# xy_plotter_circuit.net
KiCad netlist of a schematic drawn in EAGLE
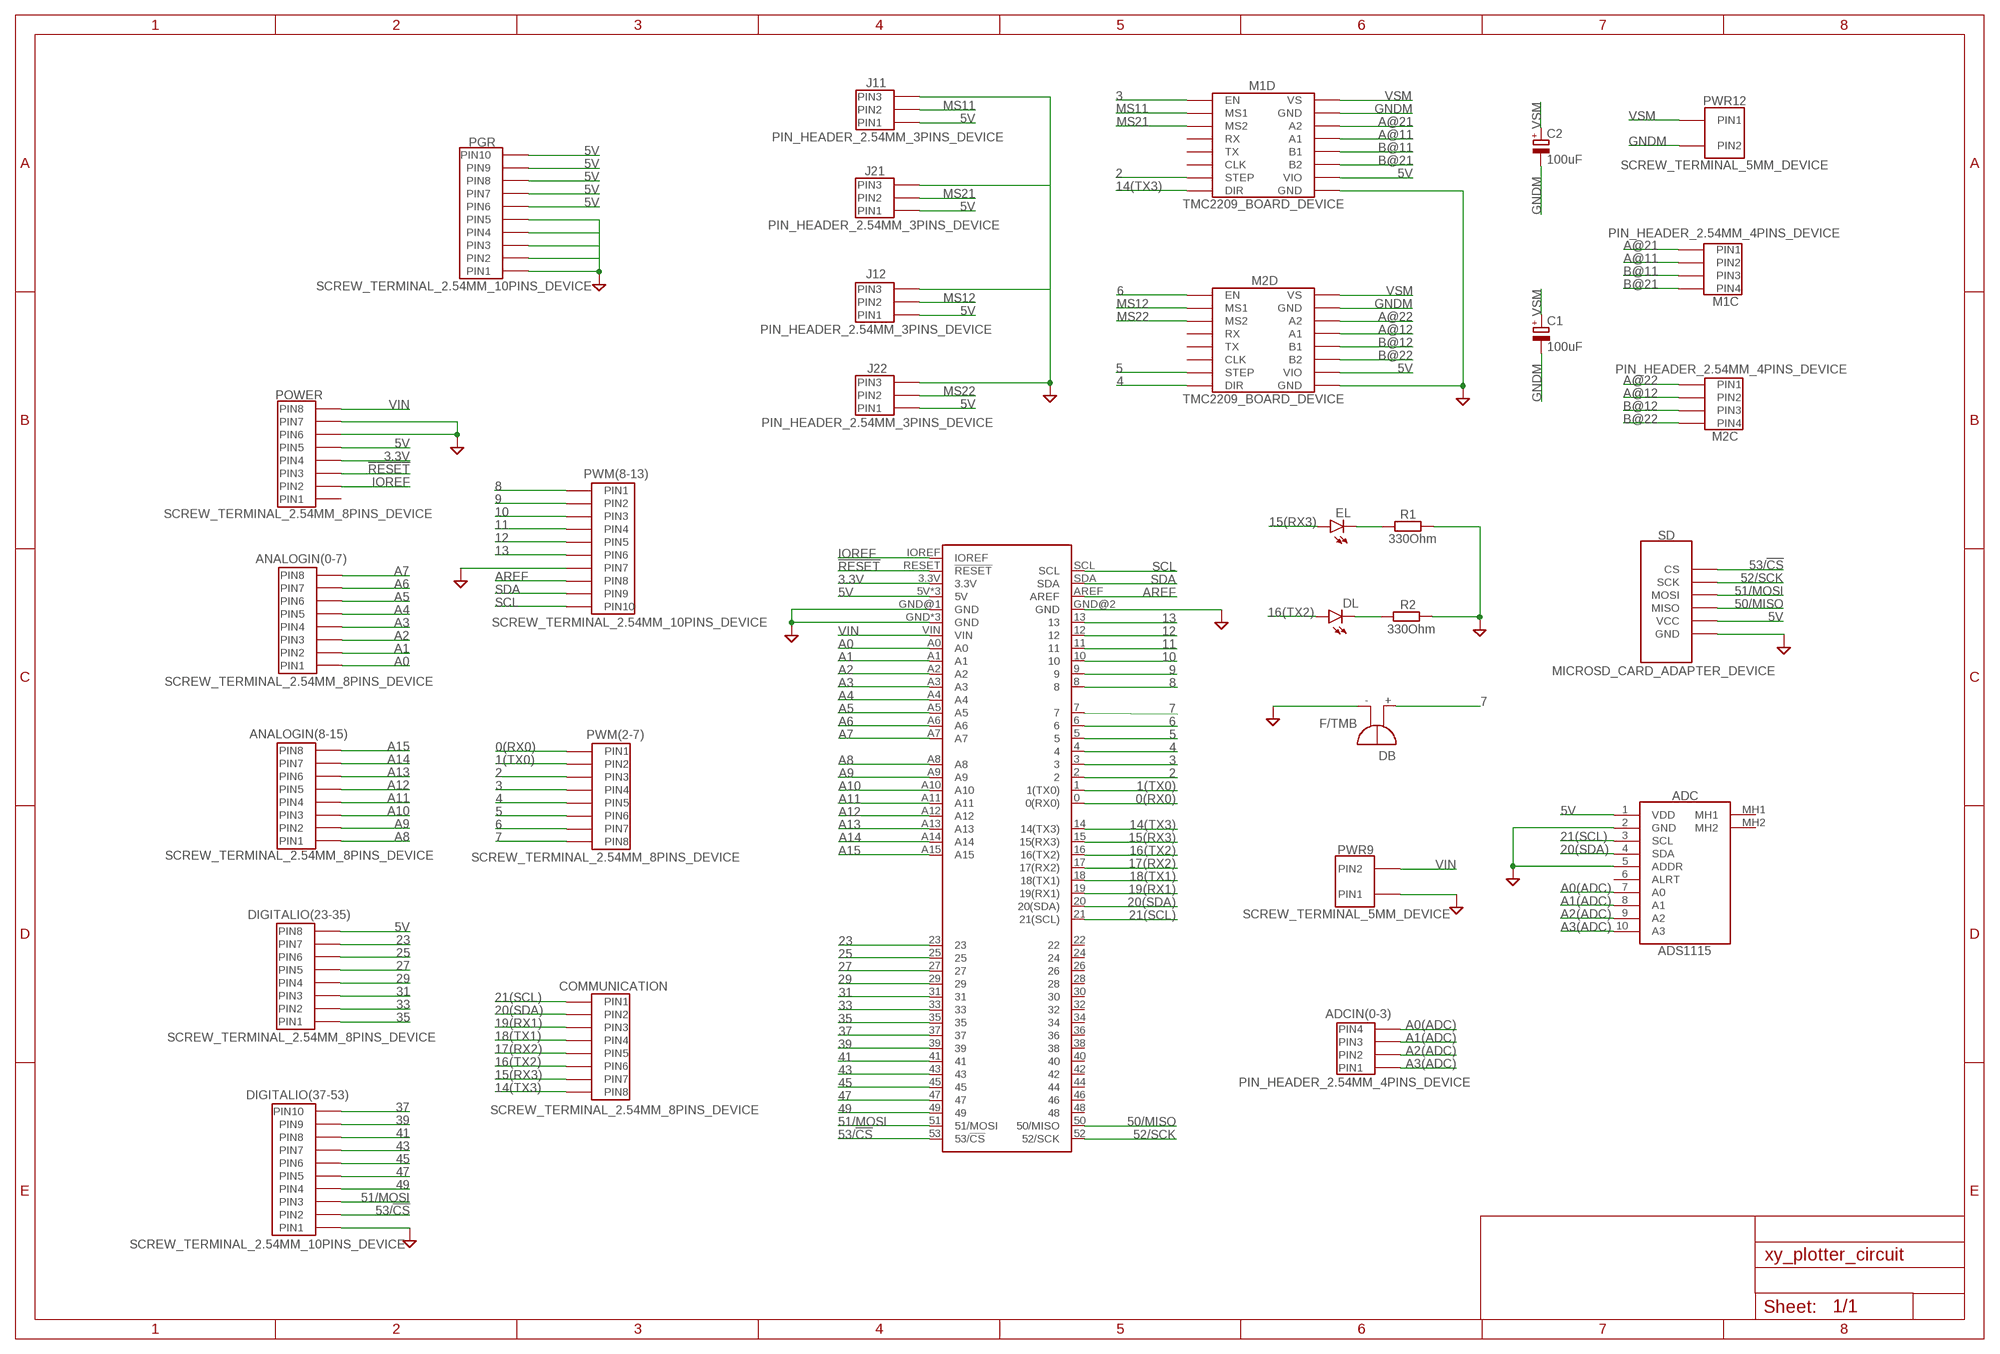
[diagram p0: schematic, sheet 1]

(export (version "E")
  (design (tool "Eeschema 10.0.6"))
  (components
    (comp (ref "ADC")
      (value "ADS1115")
      (footprint "eagle-import:ADS1115")
      (libsource (lib "eagle-import") (part "ADS1115"))
    )
    (comp (ref "ADCIN(0-3)")
      (value "PIN_HEADER_2.54MM_4PINS_DEVICE")
      (footprint "eagle-import:PIN_HEADER_2.54MM_4PINS_FOOTPRINT")
      (libsource (lib "eagle-import") (part "PIN_HEADER_2.54MM_4PINS_DEVICE"))
    )
    (comp (ref "ANALOGIN(0-7)")
      (value "SCREW_TERMINAL_2.54MM_8PINS_DEVICE")
      (footprint "eagle-import:SCREW_TERMINAL_2.54MM_8PINS_FOOTPRINT")
      (libsource (lib "eagle-import") (part "SCREW_TERMINAL_2.54MM_8PINS_DEVICE"))
    )
    (comp (ref "ANALOGIN(8-15)")
      (value "SCREW_TERMINAL_2.54MM_8PINS_DEVICE")
      (footprint "eagle-import:SCREW_TERMINAL_2.54MM_8PINS_FOOTPRINT")
      (libsource (lib "eagle-import") (part "SCREW_TERMINAL_2.54MM_8PINS_DEVICE"))
    )
    (comp (ref "ARDUINO")
      (value "ARDUINO_MEGA_R3FULL")
      (footprint "eagle-import:ARDUINO_MEGA_NO_SILK")
      (libsource (lib "eagle-import") (part "ARDUINO_MEGA_R3FULL"))
    )
    (comp (ref "C1")
      (value "100uF")
      (footprint "eagle-import:E2,5-7")
      (libsource (lib "eagle-import") (part "CPOL-EUE2.5-7"))
    )
    (comp (ref "C2")
      (value "100uF")
      (footprint "eagle-import:E2,5-7")
      (libsource (lib "eagle-import") (part "CPOL-EUE2.5-7"))
    )
    (comp (ref "COMMUNICATION")
      (value "SCREW_TERMINAL_2.54MM_8PINS_DEVICE")
      (footprint "eagle-import:SCREW_TERMINAL_2.54MM_8PINS_FOOTPRINT")
      (libsource (lib "eagle-import") (part "SCREW_TERMINAL_2.54MM_8PINS_DEVICE"))
    )
    (comp (ref "DB")
      (value "F/TMB")
      (footprint "eagle-import:F_TMB")
      (libsource (lib "eagle-import") (part "F/TMB"))
    )
    (comp (ref "DIGITALIO(23-35)")
      (value "SCREW_TERMINAL_2.54MM_8PINS_DEVICE")
      (footprint "eagle-import:SCREW_TERMINAL_2.54MM_8PINS_FOOTPRINT")
      (libsource (lib "eagle-import") (part "SCREW_TERMINAL_2.54MM_8PINS_DEVICE"))
    )
    (comp (ref "DIGITALIO(37-53)")
      (value "SCREW_TERMINAL_2.54MM_10PINS_DEVICE")
      (footprint "eagle-import:SCREW_TERMINAL_2.54MM_10PINS_FOOTPRINT")
      (libsource (lib "eagle-import") (part "SCREW_TERMINAL_2.54MM_10PINS_DEVICE"))
    )
    (comp (ref "DL")
      (value "LED3MM")
      (footprint "eagle-import:LED3MM")
      (libsource (lib "eagle-import") (part "LED3MM"))
    )
    (comp (ref "EL")
      (value "LED3MM")
      (footprint "eagle-import:LED3MM")
      (libsource (lib "eagle-import") (part "LED3MM"))
    )
    (comp (ref "J11")
      (value "PIN_HEADER_2.54MM_3PINS_DEVICE")
      (footprint "eagle-import:PIN_HEADER_2.54MM_3PINS_FOOTPRINT")
      (libsource (lib "eagle-import") (part "PIN_HEADER_2.54MM_3PINS_DEVICE"))
    )
    (comp (ref "J12")
      (value "PIN_HEADER_2.54MM_3PINS_DEVICE")
      (footprint "eagle-import:PIN_HEADER_2.54MM_3PINS_FOOTPRINT")
      (libsource (lib "eagle-import") (part "PIN_HEADER_2.54MM_3PINS_DEVICE"))
    )
    (comp (ref "J21")
      (value "PIN_HEADER_2.54MM_3PINS_DEVICE")
      (footprint "eagle-import:PIN_HEADER_2.54MM_3PINS_FOOTPRINT")
      (libsource (lib "eagle-import") (part "PIN_HEADER_2.54MM_3PINS_DEVICE"))
    )
    (comp (ref "J22")
      (value "PIN_HEADER_2.54MM_3PINS_DEVICE")
      (footprint "eagle-import:PIN_HEADER_2.54MM_3PINS_FOOTPRINT")
      (libsource (lib "eagle-import") (part "PIN_HEADER_2.54MM_3PINS_DEVICE"))
    )
    (comp (ref "M1C")
      (value "PIN_HEADER_2.54MM_4PINS_DEVICE")
      (footprint "eagle-import:PIN_HEADER_2.54MM_4PINS_FOOTPRINT")
      (libsource (lib "eagle-import") (part "PIN_HEADER_2.54MM_4PINS_DEVICE"))
    )
    (comp (ref "M1D")
      (value "TMC2209_BOARD_DEVICE")
      (footprint "eagle-import:TMC2209_BOARD_FOOTPRINT")
      (libsource (lib "eagle-import") (part "TMC2209_BOARD_DEVICE"))
    )
    (comp (ref "M2C")
      (value "PIN_HEADER_2.54MM_4PINS_DEVICE")
      (footprint "eagle-import:PIN_HEADER_2.54MM_4PINS_FOOTPRINT")
      (libsource (lib "eagle-import") (part "PIN_HEADER_2.54MM_4PINS_DEVICE"))
    )
    (comp (ref "M2D")
      (value "TMC2209_BOARD_DEVICE")
      (footprint "eagle-import:TMC2209_BOARD_FOOTPRINT")
      (libsource (lib "eagle-import") (part "TMC2209_BOARD_DEVICE"))
    )
    (comp (ref "PGR")
      (value "SCREW_TERMINAL_2.54MM_10PINS_DEVICE")
      (footprint "eagle-import:SCREW_TERMINAL_2.54MM_10PINS_FOOTPRINT")
      (libsource (lib "eagle-import") (part "SCREW_TERMINAL_2.54MM_10PINS_DEVICE"))
    )
    (comp (ref "POWER")
      (value "SCREW_TERMINAL_2.54MM_8PINS_DEVICE")
      (footprint "eagle-import:SCREW_TERMINAL_2.54MM_8PINS_FOOTPRINT")
      (libsource (lib "eagle-import") (part "SCREW_TERMINAL_2.54MM_8PINS_DEVICE"))
    )
    (comp (ref "PWM(2-7)")
      (value "SCREW_TERMINAL_2.54MM_8PINS_DEVICE")
      (footprint "eagle-import:SCREW_TERMINAL_2.54MM_8PINS_FOOTPRINT")
      (libsource (lib "eagle-import") (part "SCREW_TERMINAL_2.54MM_8PINS_DEVICE"))
    )
    (comp (ref "PWM(8-13)")
      (value "SCREW_TERMINAL_2.54MM_10PINS_DEVICE")
      (footprint "eagle-import:SCREW_TERMINAL_2.54MM_10PINS_FOOTPRINT")
      (libsource (lib "eagle-import") (part "SCREW_TERMINAL_2.54MM_10PINS_DEVICE"))
    )
    (comp (ref "PWR9")
      (value "SCREW_TERMINAL_5MM_DEVICE")
      (footprint "eagle-import:SCREW_TERMINAL_5MM_FOOTPRINT")
      (libsource (lib "eagle-import") (part "SCREW_TERMINAL_5MM_DEVICE"))
    )
    (comp (ref "PWR12")
      (value "SCREW_TERMINAL_5MM_DEVICE")
      (footprint "eagle-import:SCREW_TERMINAL_5MM_FOOTPRINT")
      (libsource (lib "eagle-import") (part "SCREW_TERMINAL_5MM_DEVICE"))
    )
    (comp (ref "R1")
      (value "330Ohm")
      (footprint "eagle-import:0207_7")
      (libsource (lib "eagle-import") (part "R-EU_0207/7"))
    )
    (comp (ref "R2")
      (value "330Ohm")
      (footprint "eagle-import:0207_7")
      (libsource (lib "eagle-import") (part "R-EU_0207/7"))
    )
    (comp (ref "SD")
      (value "MICROSD_CARD_ADAPTER_DEVICE")
      (footprint "eagle-import:MICROSD_CARD_ADAPTER_FOOTPRINT")
      (libsource (lib "eagle-import") (part "MICROSD_CARD_ADAPTER_DEVICE"))
    )
  )
  (nets
    (net (code "1") (name "/0(RX0)") (class "Default")
      (node (ref "ARDUINO") (pin "0") (pinfunction "0(RX0)_0") (pintype "bidirectional"))
      (node (ref "PWM(2-7)") (pin "PIN1") (pinfunction "PIN1_PIN1") (pintype "bidirectional"))
    )
    (net (code "2") (name "/1(TX0)") (class "Default")
      (node (ref "ARDUINO") (pin "1") (pinfunction "1(TX0)_1") (pintype "bidirectional"))
      (node (ref "PWM(2-7)") (pin "PIN2") (pinfunction "PIN2_PIN2") (pintype "bidirectional"))
    )
    (net (code "3") (name "/2") (class "Default")
      (node (ref "ARDUINO") (pin "2") (pinfunction "2_2") (pintype "bidirectional"))
      (node (ref "M1D") (pin "STEP") (pinfunction "STEP_STEP") (pintype "input"))
      (node (ref "PWM(2-7)") (pin "PIN3") (pinfunction "PIN3_PIN3") (pintype "bidirectional"))
    )
    (net (code "4") (name "/3") (class "Default")
      (node (ref "ARDUINO") (pin "3") (pinfunction "3_3") (pintype "bidirectional"))
      (node (ref "M1D") (pin "EN") (pinfunction "EN_EN") (pintype "input"))
      (node (ref "PWM(2-7)") (pin "PIN4") (pinfunction "PIN4_PIN4") (pintype "bidirectional"))
    )
    (net (code "5") (name "/3.3V") (class "Default")
      (node (ref "ARDUINO") (pin "3.3V") (pinfunction "3.3V_3.3V") (pintype "bidirectional"))
      (node (ref "POWER") (pin "PIN4") (pinfunction "PIN4_PIN4") (pintype "bidirectional"))
    )
    (net (code "6") (name "/4") (class "Default")
      (node (ref "ARDUINO") (pin "4") (pinfunction "4_4") (pintype "bidirectional"))
      (node (ref "M2D") (pin "DIR") (pinfunction "DIR_DIR") (pintype "input"))
      (node (ref "PWM(2-7)") (pin "PIN5") (pinfunction "PIN5_PIN5") (pintype "bidirectional"))
    )
    (net (code "7") (name "/5") (class "Default")
      (node (ref "ARDUINO") (pin "5") (pinfunction "5_5") (pintype "bidirectional"))
      (node (ref "M2D") (pin "STEP") (pinfunction "STEP_STEP") (pintype "input"))
      (node (ref "PWM(2-7)") (pin "PIN6") (pinfunction "PIN6_PIN6") (pintype "bidirectional"))
    )
    (net (code "8") (name "/5V") (class "Default")
      (node (ref "ADC") (pin "1") (pinfunction "VDD_1") (pintype "power_in"))
      (node (ref "ARDUINO") (pin "5V") (pinfunction "5V_5V") (pintype "bidirectional"))
      (node (ref "ARDUINO") (pin "5V@1") (pinfunction "5V_5V@1") (pintype "bidirectional"))
      (node (ref "ARDUINO") (pin "5V@2") (pinfunction "5V_5V@2") (pintype "bidirectional"))
      (node (ref "DIGITALIO(23-35)") (pin "PIN8") (pinfunction "PIN8_PIN8") (pintype "bidirectional"))
      (node (ref "J11") (pin "PIN1") (pinfunction "PIN1_PIN1") (pintype "bidirectional"))
      (node (ref "J12") (pin "PIN1") (pinfunction "PIN1_PIN1") (pintype "bidirectional"))
      (node (ref "J21") (pin "PIN1") (pinfunction "PIN1_PIN1") (pintype "bidirectional"))
      (node (ref "J22") (pin "PIN1") (pinfunction "PIN1_PIN1") (pintype "bidirectional"))
      (node (ref "M1D") (pin "VIO") (pinfunction "VIO_VIO") (pintype "power_in"))
      (node (ref "M2D") (pin "VIO") (pinfunction "VIO_VIO") (pintype "power_in"))
      (node (ref "PGR") (pin "PIN10") (pinfunction "PIN10_PIN10") (pintype "bidirectional"))
      (node (ref "PGR") (pin "PIN6") (pinfunction "PIN6_PIN6") (pintype "bidirectional"))
      (node (ref "PGR") (pin "PIN7") (pinfunction "PIN7_PIN7") (pintype "bidirectional"))
      (node (ref "PGR") (pin "PIN8") (pinfunction "PIN8_PIN8") (pintype "bidirectional"))
      (node (ref "PGR") (pin "PIN9") (pinfunction "PIN9_PIN9") (pintype "bidirectional"))
      (node (ref "POWER") (pin "PIN5") (pinfunction "PIN5_PIN5") (pintype "bidirectional"))
      (node (ref "SD") (pin "VCC") (pinfunction "VCC_VCC") (pintype "power_in"))
    )
    (net (code "9") (name "/6") (class "Default")
      (node (ref "ARDUINO") (pin "6") (pinfunction "6_6") (pintype "bidirectional"))
      (node (ref "M2D") (pin "EN") (pinfunction "EN_EN") (pintype "input"))
      (node (ref "PWM(2-7)") (pin "PIN7") (pinfunction "PIN7_PIN7") (pintype "bidirectional"))
    )
    (net (code "10") (name "/7") (class "Default")
      (node (ref "ARDUINO") (pin "7") (pinfunction "7_7") (pintype "bidirectional"))
      (node (ref "DB") (pin "+") (pinfunction "+_+") (pintype "passive"))
      (node (ref "PWM(2-7)") (pin "PIN8") (pinfunction "PIN8_PIN8") (pintype "bidirectional"))
    )
    (net (code "11") (name "/8") (class "Default")
      (node (ref "ARDUINO") (pin "8") (pinfunction "8_8") (pintype "bidirectional"))
      (node (ref "PWM(8-13)") (pin "PIN1") (pinfunction "PIN1_PIN1") (pintype "bidirectional"))
    )
    (net (code "12") (name "/9") (class "Default")
      (node (ref "ARDUINO") (pin "9") (pinfunction "9_9") (pintype "bidirectional"))
      (node (ref "PWM(8-13)") (pin "PIN2") (pinfunction "PIN2_PIN2") (pintype "bidirectional"))
    )
    (net (code "13") (name "/10") (class "Default")
      (node (ref "ARDUINO") (pin "10") (pinfunction "10_10") (pintype "bidirectional"))
      (node (ref "PWM(8-13)") (pin "PIN3") (pinfunction "PIN3_PIN3") (pintype "bidirectional"))
    )
    (net (code "14") (name "/11") (class "Default")
      (node (ref "ARDUINO") (pin "11") (pinfunction "11_11") (pintype "bidirectional"))
      (node (ref "PWM(8-13)") (pin "PIN4") (pinfunction "PIN4_PIN4") (pintype "bidirectional"))
    )
    (net (code "15") (name "/12") (class "Default")
      (node (ref "ARDUINO") (pin "12") (pinfunction "12_12") (pintype "bidirectional"))
      (node (ref "PWM(8-13)") (pin "PIN5") (pinfunction "PIN5_PIN5") (pintype "bidirectional"))
    )
    (net (code "16") (name "/13") (class "Default")
      (node (ref "ARDUINO") (pin "13") (pinfunction "13_13") (pintype "bidirectional"))
      (node (ref "PWM(8-13)") (pin "PIN6") (pinfunction "PIN6_PIN6") (pintype "bidirectional"))
    )
    (net (code "17") (name "/14(TX3)") (class "Default")
      (node (ref "ARDUINO") (pin "14") (pinfunction "14(TX3)_14") (pintype "bidirectional"))
      (node (ref "COMMUNICATION") (pin "PIN8") (pinfunction "PIN8_PIN8") (pintype "bidirectional"))
      (node (ref "M1D") (pin "DIR") (pinfunction "DIR_DIR") (pintype "input"))
    )
    (net (code "18") (name "/15(RX3)") (class "Default")
      (node (ref "ARDUINO") (pin "15") (pinfunction "15(RX3)_15") (pintype "bidirectional"))
      (node (ref "COMMUNICATION") (pin "PIN7") (pinfunction "PIN7_PIN7") (pintype "bidirectional"))
      (node (ref "EL") (pin "A") (pinfunction "A_A") (pintype "passive"))
    )
    (net (code "19") (name "/16(TX2)") (class "Default")
      (node (ref "ARDUINO") (pin "16") (pinfunction "16(TX2)_16") (pintype "bidirectional"))
      (node (ref "COMMUNICATION") (pin "PIN6") (pinfunction "PIN6_PIN6") (pintype "bidirectional"))
      (node (ref "DL") (pin "A") (pinfunction "A_A") (pintype "passive"))
    )
    (net (code "20") (name "/17(RX2)") (class "Default")
      (node (ref "ARDUINO") (pin "17") (pinfunction "17(RX2)_17") (pintype "bidirectional"))
      (node (ref "COMMUNICATION") (pin "PIN5") (pinfunction "PIN5_PIN5") (pintype "bidirectional"))
    )
    (net (code "21") (name "/18(TX1)") (class "Default")
      (node (ref "ARDUINO") (pin "18") (pinfunction "18(TX1)_18") (pintype "bidirectional"))
      (node (ref "COMMUNICATION") (pin "PIN4") (pinfunction "PIN4_PIN4") (pintype "bidirectional"))
    )
    (net (code "22") (name "/19(RX1)") (class "Default")
      (node (ref "ARDUINO") (pin "19") (pinfunction "19(RX1)_19") (pintype "bidirectional"))
      (node (ref "COMMUNICATION") (pin "PIN3") (pinfunction "PIN3_PIN3") (pintype "bidirectional"))
    )
    (net (code "23") (name "/20(SDA)") (class "Default")
      (node (ref "ADC") (pin "4") (pinfunction "SDA_4") (pintype "bidirectional"))
      (node (ref "ARDUINO") (pin "20") (pinfunction "20(SDA)_20") (pintype "bidirectional"))
      (node (ref "COMMUNICATION") (pin "PIN2") (pinfunction "PIN2_PIN2") (pintype "bidirectional"))
    )
    (net (code "24") (name "/21(SCL)") (class "Default")
      (node (ref "ADC") (pin "3") (pinfunction "SCL_3") (pintype "input"))
      (node (ref "ARDUINO") (pin "21") (pinfunction "21(SCL)_21") (pintype "bidirectional"))
      (node (ref "COMMUNICATION") (pin "PIN1") (pinfunction "PIN1_PIN1") (pintype "bidirectional"))
    )
    (net (code "25") (name "/23") (class "Default")
      (node (ref "ARDUINO") (pin "23") (pinfunction "23_23") (pintype "bidirectional"))
      (node (ref "DIGITALIO(23-35)") (pin "PIN7") (pinfunction "PIN7_PIN7") (pintype "bidirectional"))
    )
    (net (code "26") (name "/25") (class "Default")
      (node (ref "ARDUINO") (pin "25") (pinfunction "25_25") (pintype "bidirectional"))
      (node (ref "DIGITALIO(23-35)") (pin "PIN6") (pinfunction "PIN6_PIN6") (pintype "bidirectional"))
    )
    (net (code "27") (name "/27") (class "Default")
      (node (ref "ARDUINO") (pin "27") (pinfunction "27_27") (pintype "bidirectional"))
      (node (ref "DIGITALIO(23-35)") (pin "PIN5") (pinfunction "PIN5_PIN5") (pintype "bidirectional"))
    )
    (net (code "28") (name "/29") (class "Default")
      (node (ref "ARDUINO") (pin "29") (pinfunction "29_29") (pintype "bidirectional"))
      (node (ref "DIGITALIO(23-35)") (pin "PIN4") (pinfunction "PIN4_PIN4") (pintype "bidirectional"))
    )
    (net (code "29") (name "/31") (class "Default")
      (node (ref "ARDUINO") (pin "31") (pinfunction "31_31") (pintype "bidirectional"))
      (node (ref "DIGITALIO(23-35)") (pin "PIN3") (pinfunction "PIN3_PIN3") (pintype "bidirectional"))
    )
    (net (code "30") (name "/33") (class "Default")
      (node (ref "ARDUINO") (pin "33") (pinfunction "33_33") (pintype "bidirectional"))
      (node (ref "DIGITALIO(23-35)") (pin "PIN2") (pinfunction "PIN2_PIN2") (pintype "bidirectional"))
    )
    (net (code "31") (name "/35") (class "Default")
      (node (ref "ARDUINO") (pin "35") (pinfunction "35_35") (pintype "bidirectional"))
      (node (ref "DIGITALIO(23-35)") (pin "PIN1") (pinfunction "PIN1_PIN1") (pintype "bidirectional"))
    )
    (net (code "32") (name "/37") (class "Default")
      (node (ref "ARDUINO") (pin "37") (pinfunction "37_37") (pintype "bidirectional"))
      (node (ref "DIGITALIO(37-53)") (pin "PIN10") (pinfunction "PIN10_PIN10") (pintype "bidirectional"))
    )
    (net (code "33") (name "/39") (class "Default")
      (node (ref "ARDUINO") (pin "39") (pinfunction "39_39") (pintype "bidirectional"))
      (node (ref "DIGITALIO(37-53)") (pin "PIN9") (pinfunction "PIN9_PIN9") (pintype "bidirectional"))
    )
    (net (code "34") (name "/41") (class "Default")
      (node (ref "ARDUINO") (pin "41") (pinfunction "41_41") (pintype "bidirectional"))
      (node (ref "DIGITALIO(37-53)") (pin "PIN8") (pinfunction "PIN8_PIN8") (pintype "bidirectional"))
    )
    (net (code "35") (name "/43") (class "Default")
      (node (ref "ARDUINO") (pin "43") (pinfunction "43_43") (pintype "bidirectional"))
      (node (ref "DIGITALIO(37-53)") (pin "PIN7") (pinfunction "PIN7_PIN7") (pintype "bidirectional"))
    )
    (net (code "36") (name "/45") (class "Default")
      (node (ref "ARDUINO") (pin "45") (pinfunction "45_45") (pintype "bidirectional"))
      (node (ref "DIGITALIO(37-53)") (pin "PIN6") (pinfunction "PIN6_PIN6") (pintype "bidirectional"))
    )
    (net (code "37") (name "/47") (class "Default")
      (node (ref "ARDUINO") (pin "47") (pinfunction "47_47") (pintype "bidirectional"))
      (node (ref "DIGITALIO(37-53)") (pin "PIN5") (pinfunction "PIN5_PIN5") (pintype "bidirectional"))
    )
    (net (code "38") (name "/49") (class "Default")
      (node (ref "ARDUINO") (pin "49") (pinfunction "49_49") (pintype "bidirectional"))
      (node (ref "DIGITALIO(37-53)") (pin "PIN4") (pinfunction "PIN4_PIN4") (pintype "bidirectional"))
    )
    (net (code "39") (name "/50{slash}MISO") (class "Default")
      (node (ref "ARDUINO") (pin "50") (pinfunction "50/MISO_50") (pintype "bidirectional"))
      (node (ref "SD") (pin "MISO") (pinfunction "MISO_MISO") (pintype "output"))
    )
    (net (code "40") (name "/51{slash}MOSI") (class "Default")
      (node (ref "ARDUINO") (pin "51") (pinfunction "51/MOSI_51") (pintype "bidirectional"))
      (node (ref "DIGITALIO(37-53)") (pin "PIN3") (pinfunction "PIN3_PIN3") (pintype "bidirectional"))
      (node (ref "SD") (pin "MOSI") (pinfunction "MOSI_MOSI") (pintype "input"))
    )
    (net (code "41") (name "/52{slash}SCK") (class "Default")
      (node (ref "ARDUINO") (pin "52") (pinfunction "52/SCK_52") (pintype "bidirectional"))
      (node (ref "SD") (pin "SCK") (pinfunction "SCK_SCK") (pintype "input"))
    )
    (net (code "42") (name "/53{slash}~{CS}") (class "Default")
      (node (ref "ARDUINO") (pin "53") (pinfunction "53/~{CS}_53") (pintype "bidirectional"))
      (node (ref "DIGITALIO(37-53)") (pin "PIN2") (pinfunction "PIN2_PIN2") (pintype "bidirectional"))
      (node (ref "SD") (pin "CS") (pinfunction "CS_CS") (pintype "input"))
    )
    (net (code "43") (name "/A0") (class "Default")
      (node (ref "ANALOGIN(0-7)") (pin "PIN1") (pinfunction "PIN1_PIN1") (pintype "bidirectional"))
      (node (ref "ARDUINO") (pin "A0") (pinfunction "A0_A0") (pintype "bidirectional"))
    )
    (net (code "44") (name "/A0(ADC)") (class "Default")
      (node (ref "ADC") (pin "7") (pinfunction "A0_7") (pintype "input"))
      (node (ref "ADCIN(0-3)") (pin "PIN4") (pinfunction "PIN4_PIN4") (pintype "bidirectional"))
    )
    (net (code "45") (name "/A1") (class "Default")
      (node (ref "ANALOGIN(0-7)") (pin "PIN2") (pinfunction "PIN2_PIN2") (pintype "bidirectional"))
      (node (ref "ARDUINO") (pin "A1") (pinfunction "A1_A1") (pintype "bidirectional"))
    )
    (net (code "46") (name "/A1(ADC)") (class "Default")
      (node (ref "ADC") (pin "8") (pinfunction "A1_8") (pintype "input"))
      (node (ref "ADCIN(0-3)") (pin "PIN3") (pinfunction "PIN3_PIN3") (pintype "bidirectional"))
    )
    (net (code "47") (name "/A2") (class "Default")
      (node (ref "ANALOGIN(0-7)") (pin "PIN3") (pinfunction "PIN3_PIN3") (pintype "bidirectional"))
      (node (ref "ARDUINO") (pin "A2") (pinfunction "A2_A2") (pintype "bidirectional"))
    )
    (net (code "48") (name "/A2(ADC)") (class "Default")
      (node (ref "ADC") (pin "9") (pinfunction "A2_9") (pintype "input"))
      (node (ref "ADCIN(0-3)") (pin "PIN2") (pinfunction "PIN2_PIN2") (pintype "bidirectional"))
    )
    (net (code "49") (name "/A3") (class "Default")
      (node (ref "ANALOGIN(0-7)") (pin "PIN4") (pinfunction "PIN4_PIN4") (pintype "bidirectional"))
      (node (ref "ARDUINO") (pin "A3") (pinfunction "A3_A3") (pintype "bidirectional"))
    )
    (net (code "50") (name "/A3(ADC)") (class "Default")
      (node (ref "ADC") (pin "10") (pinfunction "A3_10") (pintype "input"))
      (node (ref "ADCIN(0-3)") (pin "PIN1") (pinfunction "PIN1_PIN1") (pintype "bidirectional"))
    )
    (net (code "51") (name "/A4") (class "Default")
      (node (ref "ANALOGIN(0-7)") (pin "PIN5") (pinfunction "PIN5_PIN5") (pintype "bidirectional"))
      (node (ref "ARDUINO") (pin "A4") (pinfunction "A4_A4") (pintype "bidirectional"))
    )
    (net (code "52") (name "/A5") (class "Default")
      (node (ref "ANALOGIN(0-7)") (pin "PIN6") (pinfunction "PIN6_PIN6") (pintype "bidirectional"))
      (node (ref "ARDUINO") (pin "A5") (pinfunction "A5_A5") (pintype "bidirectional"))
    )
    (net (code "53") (name "/A6") (class "Default")
      (node (ref "ANALOGIN(0-7)") (pin "PIN7") (pinfunction "PIN7_PIN7") (pintype "bidirectional"))
      (node (ref "ARDUINO") (pin "A6") (pinfunction "A6_A6") (pintype "bidirectional"))
    )
    (net (code "54") (name "/A7") (class "Default")
      (node (ref "ANALOGIN(0-7)") (pin "PIN8") (pinfunction "PIN8_PIN8") (pintype "bidirectional"))
      (node (ref "ARDUINO") (pin "A7") (pinfunction "A7_A7") (pintype "bidirectional"))
    )
    (net (code "55") (name "/A8") (class "Default")
      (node (ref "ANALOGIN(8-15)") (pin "PIN1") (pinfunction "PIN1_PIN1") (pintype "bidirectional"))
      (node (ref "ARDUINO") (pin "A8") (pinfunction "A8_A8") (pintype "bidirectional"))
    )
    (net (code "56") (name "/A9") (class "Default")
      (node (ref "ANALOGIN(8-15)") (pin "PIN2") (pinfunction "PIN2_PIN2") (pintype "bidirectional"))
      (node (ref "ARDUINO") (pin "A9") (pinfunction "A9_A9") (pintype "bidirectional"))
    )
    (net (code "57") (name "/A10") (class "Default")
      (node (ref "ANALOGIN(8-15)") (pin "PIN3") (pinfunction "PIN3_PIN3") (pintype "bidirectional"))
      (node (ref "ARDUINO") (pin "A10") (pinfunction "A10_A10") (pintype "bidirectional"))
    )
    (net (code "58") (name "/A11") (class "Default")
      (node (ref "ANALOGIN(8-15)") (pin "PIN4") (pinfunction "PIN4_PIN4") (pintype "bidirectional"))
      (node (ref "ARDUINO") (pin "A11") (pinfunction "A11_A11") (pintype "bidirectional"))
    )
    (net (code "59") (name "/A12") (class "Default")
      (node (ref "ANALOGIN(8-15)") (pin "PIN5") (pinfunction "PIN5_PIN5") (pintype "bidirectional"))
      (node (ref "ARDUINO") (pin "A12") (pinfunction "A12_A12") (pintype "bidirectional"))
    )
    (net (code "60") (name "/A13") (class "Default")
      (node (ref "ANALOGIN(8-15)") (pin "PIN6") (pinfunction "PIN6_PIN6") (pintype "bidirectional"))
      (node (ref "ARDUINO") (pin "A13") (pinfunction "A13_A13") (pintype "bidirectional"))
    )
    (net (code "61") (name "/A14") (class "Default")
      (node (ref "ANALOGIN(8-15)") (pin "PIN7") (pinfunction "PIN7_PIN7") (pintype "bidirectional"))
      (node (ref "ARDUINO") (pin "A14") (pinfunction "A14_A14") (pintype "bidirectional"))
    )
    (net (code "62") (name "/A15") (class "Default")
      (node (ref "ANALOGIN(8-15)") (pin "PIN8") (pinfunction "PIN8_PIN8") (pintype "bidirectional"))
      (node (ref "ARDUINO") (pin "A15") (pinfunction "A15_A15") (pintype "bidirectional"))
    )
    (net (code "63") (name "/A@11") (class "Default")
      (node (ref "M1C") (pin "PIN2") (pinfunction "PIN2_PIN2") (pintype "bidirectional"))
      (node (ref "M1D") (pin "A1") (pinfunction "A1_A1") (pintype "bidirectional"))
    )
    (net (code "64") (name "/A@12") (class "Default")
      (node (ref "M2C") (pin "PIN2") (pinfunction "PIN2_PIN2") (pintype "bidirectional"))
      (node (ref "M2D") (pin "A1") (pinfunction "A1_A1") (pintype "bidirectional"))
    )
    (net (code "65") (name "/A@21") (class "Default")
      (node (ref "M1C") (pin "PIN1") (pinfunction "PIN1_PIN1") (pintype "bidirectional"))
      (node (ref "M1D") (pin "A2") (pinfunction "A2_A2") (pintype "bidirectional"))
    )
    (net (code "66") (name "/A@22") (class "Default")
      (node (ref "M2C") (pin "PIN1") (pinfunction "PIN1_PIN1") (pintype "bidirectional"))
      (node (ref "M2D") (pin "A2") (pinfunction "A2_A2") (pintype "bidirectional"))
    )
    (net (code "67") (name "/AREF") (class "Default")
      (node (ref "ARDUINO") (pin "AREF") (pinfunction "AREF_AREF") (pintype "bidirectional"))
      (node (ref "PWM(8-13)") (pin "PIN8") (pinfunction "PIN8_PIN8") (pintype "bidirectional"))
    )
    (net (code "68") (name "/B@11") (class "Default")
      (node (ref "M1C") (pin "PIN3") (pinfunction "PIN3_PIN3") (pintype "bidirectional"))
      (node (ref "M1D") (pin "B1") (pinfunction "B1_B1") (pintype "bidirectional"))
    )
    (net (code "69") (name "/B@12") (class "Default")
      (node (ref "M2C") (pin "PIN3") (pinfunction "PIN3_PIN3") (pintype "bidirectional"))
      (node (ref "M2D") (pin "B1") (pinfunction "B1_B1") (pintype "bidirectional"))
    )
    (net (code "70") (name "/B@21") (class "Default")
      (node (ref "M1C") (pin "PIN4") (pinfunction "PIN4_PIN4") (pintype "bidirectional"))
      (node (ref "M1D") (pin "B2") (pinfunction "B2_B2") (pintype "bidirectional"))
    )
    (net (code "71") (name "/B@22") (class "Default")
      (node (ref "M2C") (pin "PIN4") (pinfunction "PIN4_PIN4") (pintype "bidirectional"))
      (node (ref "M2D") (pin "B2") (pinfunction "B2_B2") (pintype "bidirectional"))
    )
    (net (code "72") (name "/GNDM") (class "Default")
      (node (ref "C1") (pin "-") (pinfunction "-_-") (pintype "passive"))
      (node (ref "C2") (pin "-") (pinfunction "-_-") (pintype "passive"))
      (node (ref "M1D") (pin "GND@1") (pinfunction "GND_GND@1") (pintype "power_in"))
      (node (ref "M2D") (pin "GND@1") (pinfunction "GND_GND@1") (pintype "power_in"))
      (node (ref "PWR12") (pin "PIN2") (pinfunction "PIN2_PIN2") (pintype "bidirectional"))
    )
    (net (code "73") (name "/IOREF") (class "Default")
      (node (ref "ARDUINO") (pin "IOREF") (pinfunction "IOREF_IOREF") (pintype "bidirectional"))
      (node (ref "POWER") (pin "PIN2") (pinfunction "PIN2_PIN2") (pintype "bidirectional"))
    )
    (net (code "74") (name "/MS11") (class "Default")
      (node (ref "J11") (pin "PIN2") (pinfunction "PIN2_PIN2") (pintype "bidirectional"))
      (node (ref "M1D") (pin "MS1") (pinfunction "MS1_MS1") (pintype "input"))
    )
    (net (code "75") (name "/MS12") (class "Default")
      (node (ref "J12") (pin "PIN2") (pinfunction "PIN2_PIN2") (pintype "bidirectional"))
      (node (ref "M2D") (pin "MS1") (pinfunction "MS1_MS1") (pintype "input"))
    )
    (net (code "76") (name "/MS21") (class "Default")
      (node (ref "J21") (pin "PIN2") (pinfunction "PIN2_PIN2") (pintype "bidirectional"))
      (node (ref "M1D") (pin "MS2") (pinfunction "MS2_MS2") (pintype "input"))
    )
    (net (code "77") (name "/MS22") (class "Default")
      (node (ref "J22") (pin "PIN2") (pinfunction "PIN2_PIN2") (pintype "bidirectional"))
      (node (ref "M2D") (pin "MS2") (pinfunction "MS2_MS2") (pintype "input"))
    )
    (net (code "78") (name "/SCL") (class "Default")
      (node (ref "ARDUINO") (pin "SCL") (pinfunction "SCL_SCL") (pintype "bidirectional"))
      (node (ref "PWM(8-13)") (pin "PIN10") (pinfunction "PIN10_PIN10") (pintype "bidirectional"))
    )
    (net (code "79") (name "/SDA") (class "Default")
      (node (ref "ARDUINO") (pin "SDA") (pinfunction "SDA_SDA") (pintype "bidirectional"))
      (node (ref "PWM(8-13)") (pin "PIN9") (pinfunction "PIN9_PIN9") (pintype "bidirectional"))
    )
    (net (code "80") (name "/VIN") (class "Default")
      (node (ref "ARDUINO") (pin "VIN") (pinfunction "VIN_VIN") (pintype "bidirectional"))
      (node (ref "POWER") (pin "PIN8") (pinfunction "PIN8_PIN8") (pintype "bidirectional"))
      (node (ref "PWR9") (pin "PIN2") (pinfunction "PIN2_PIN2") (pintype "bidirectional"))
    )
    (net (code "81") (name "/VSM") (class "Default")
      (node (ref "C1") (pin "+") (pinfunction "+_+") (pintype "passive"))
      (node (ref "C2") (pin "+") (pinfunction "+_+") (pintype "passive"))
      (node (ref "M1D") (pin "VS") (pinfunction "VS_VS") (pintype "power_in"))
      (node (ref "M2D") (pin "VS") (pinfunction "VS_VS") (pintype "power_in"))
      (node (ref "PWR12") (pin "PIN1") (pinfunction "PIN1_PIN1") (pintype "bidirectional"))
    )
    (net (code "82") (name "/~{RESET}") (class "Default")
      (node (ref "ARDUINO") (pin "RESET") (pinfunction "~{RESET}_RESET") (pintype "bidirectional"))
      (node (ref "POWER") (pin "PIN3") (pinfunction "PIN3_PIN3") (pintype "bidirectional"))
    )
    (net (code "83") (name "GND") (class "Default")
      (node (ref "ADC") (pin "2") (pinfunction "GND_2") (pintype "power_in"))
      (node (ref "ADC") (pin "5") (pinfunction "ADDR_5") (pintype "input"))
      (node (ref "ARDUINO") (pin "GND") (pinfunction "GND_GND") (pintype "bidirectional"))
      (node (ref "ARDUINO") (pin "GND@1") (pinfunction "GND_GND@1") (pintype "bidirectional"))
      (node (ref "ARDUINO") (pin "GND@2") (pinfunction "GND_GND@2") (pintype "bidirectional"))
      (node (ref "ARDUINO") (pin "GND@3") (pinfunction "GND_GND@3") (pintype "bidirectional"))
      (node (ref "ARDUINO") (pin "GND@4") (pinfunction "GND_GND@4") (pintype "bidirectional"))
      (node (ref "DB") (pin "-") (pinfunction "-_-") (pintype "passive"))
      (node (ref "DIGITALIO(37-53)") (pin "PIN1") (pinfunction "PIN1_PIN1") (pintype "bidirectional"))
      (node (ref "J11") (pin "PIN3") (pinfunction "PIN3_PIN3") (pintype "bidirectional"))
      (node (ref "J12") (pin "PIN3") (pinfunction "PIN3_PIN3") (pintype "bidirectional"))
      (node (ref "J21") (pin "PIN3") (pinfunction "PIN3_PIN3") (pintype "bidirectional"))
      (node (ref "J22") (pin "PIN3") (pinfunction "PIN3_PIN3") (pintype "bidirectional"))
      (node (ref "M1D") (pin "GND@2") (pinfunction "GND_GND@2") (pintype "power_in"))
      (node (ref "M2D") (pin "GND@2") (pinfunction "GND_GND@2") (pintype "power_in"))
      (node (ref "PGR") (pin "PIN1") (pinfunction "PIN1_PIN1") (pintype "bidirectional"))
      (node (ref "PGR") (pin "PIN2") (pinfunction "PIN2_PIN2") (pintype "bidirectional"))
      (node (ref "PGR") (pin "PIN3") (pinfunction "PIN3_PIN3") (pintype "bidirectional"))
      (node (ref "PGR") (pin "PIN4") (pinfunction "PIN4_PIN4") (pintype "bidirectional"))
      (node (ref "PGR") (pin "PIN5") (pinfunction "PIN5_PIN5") (pintype "bidirectional"))
      (node (ref "POWER") (pin "PIN6") (pinfunction "PIN6_PIN6") (pintype "bidirectional"))
      (node (ref "POWER") (pin "PIN7") (pinfunction "PIN7_PIN7") (pintype "bidirectional"))
      (node (ref "PWM(8-13)") (pin "PIN7") (pinfunction "PIN7_PIN7") (pintype "bidirectional"))
      (node (ref "PWR9") (pin "PIN1") (pinfunction "PIN1_PIN1") (pintype "bidirectional"))
      (node (ref "R1") (pin "2") (pinfunction "2_2") (pintype "passive"))
      (node (ref "R2") (pin "2") (pinfunction "2_2") (pintype "passive"))
      (node (ref "SD") (pin "GND") (pinfunction "GND_GND") (pintype "power_in"))
    )
    (net (code "84") (name "Net-(DL-C)") (class "Default")
      (node (ref "DL") (pin "K") (pinfunction "C_K") (pintype "passive"))
      (node (ref "R2") (pin "1") (pinfunction "1_1") (pintype "passive"))
    )
    (net (code "85") (name "Net-(EL-C)") (class "Default")
      (node (ref "EL") (pin "K") (pinfunction "C_K") (pintype "passive"))
      (node (ref "R1") (pin "1") (pinfunction "1_1") (pintype "passive"))
    )
    (net (code "86") (name "unconnected-(ADC-ALRT-Pad6)") (class "Default")
      (node (ref "ADC") (pin "6") (pinfunction "ALRT_6") (pintype "bidirectional"))
    )
    (net (code "87") (name "unconnected-(ADC-PadMH1)") (class "Default")
      (node (ref "ADC") (pin "MH1") (pinfunction "MH1_MH1") (pintype "bidirectional"))
    )
    (net (code "88") (name "unconnected-(ADC-PadMH2)") (class "Default")
      (node (ref "ADC") (pin "MH2") (pinfunction "MH2_MH2") (pintype "bidirectional"))
    )
    (net (code "89") (name "unconnected-(ARDUINO-Pad22)") (class "Default")
      (node (ref "ARDUINO") (pin "22") (pinfunction "22_22") (pintype "bidirectional"))
    )
    (net (code "90") (name "unconnected-(ARDUINO-Pad24)") (class "Default")
      (node (ref "ARDUINO") (pin "24") (pinfunction "24_24") (pintype "bidirectional"))
    )
    (net (code "91") (name "unconnected-(ARDUINO-Pad26)") (class "Default")
      (node (ref "ARDUINO") (pin "26") (pinfunction "26_26") (pintype "bidirectional"))
    )
    (net (code "92") (name "unconnected-(ARDUINO-Pad28)") (class "Default")
      (node (ref "ARDUINO") (pin "28") (pinfunction "28_28") (pintype "bidirectional"))
    )
    (net (code "93") (name "unconnected-(ARDUINO-Pad30)") (class "Default")
      (node (ref "ARDUINO") (pin "30") (pinfunction "30_30") (pintype "bidirectional"))
    )
    (net (code "94") (name "unconnected-(ARDUINO-Pad32)") (class "Default")
      (node (ref "ARDUINO") (pin "32") (pinfunction "32_32") (pintype "bidirectional"))
    )
    (net (code "95") (name "unconnected-(ARDUINO-Pad34)") (class "Default")
      (node (ref "ARDUINO") (pin "34") (pinfunction "34_34") (pintype "bidirectional"))
    )
    (net (code "96") (name "unconnected-(ARDUINO-Pad36)") (class "Default")
      (node (ref "ARDUINO") (pin "36") (pinfunction "36_36") (pintype "bidirectional"))
    )
    (net (code "97") (name "unconnected-(ARDUINO-Pad38)") (class "Default")
      (node (ref "ARDUINO") (pin "38") (pinfunction "38_38") (pintype "bidirectional"))
    )
    (net (code "98") (name "unconnected-(ARDUINO-Pad40)") (class "Default")
      (node (ref "ARDUINO") (pin "40") (pinfunction "40_40") (pintype "bidirectional"))
    )
    (net (code "99") (name "unconnected-(ARDUINO-Pad42)") (class "Default")
      (node (ref "ARDUINO") (pin "42") (pinfunction "42_42") (pintype "bidirectional"))
    )
    (net (code "100") (name "unconnected-(ARDUINO-Pad44)") (class "Default")
      (node (ref "ARDUINO") (pin "44") (pinfunction "44_44") (pintype "bidirectional"))
    )
    (net (code "101") (name "unconnected-(ARDUINO-Pad46)") (class "Default")
      (node (ref "ARDUINO") (pin "46") (pinfunction "46_46") (pintype "bidirectional"))
    )
    (net (code "102") (name "unconnected-(ARDUINO-Pad48)") (class "Default")
      (node (ref "ARDUINO") (pin "48") (pinfunction "48_48") (pintype "bidirectional"))
    )
    (net (code "103") (name "unconnected-(M1D-PadCLK)") (class "Default")
      (node (ref "M1D") (pin "CLK") (pinfunction "CLK_CLK") (pintype "input"))
    )
    (net (code "104") (name "unconnected-(M1D-PadRX)") (class "Default")
      (node (ref "M1D") (pin "RX") (pinfunction "RX_RX") (pintype "input"))
    )
    (net (code "105") (name "unconnected-(M1D-PadTX)") (class "Default")
      (node (ref "M1D") (pin "TX") (pinfunction "TX_TX") (pintype "output"))
    )
    (net (code "106") (name "unconnected-(M2D-PadCLK)") (class "Default")
      (node (ref "M2D") (pin "CLK") (pinfunction "CLK_CLK") (pintype "input"))
    )
    (net (code "107") (name "unconnected-(M2D-PadRX)") (class "Default")
      (node (ref "M2D") (pin "RX") (pinfunction "RX_RX") (pintype "input"))
    )
    (net (code "108") (name "unconnected-(M2D-PadTX)") (class "Default")
      (node (ref "M2D") (pin "TX") (pinfunction "TX_TX") (pintype "output"))
    )
    (net (code "109") (name "unconnected-(POWER-PadPIN1)") (class "Default")
      (node (ref "POWER") (pin "PIN1") (pinfunction "PIN1_PIN1") (pintype "bidirectional"))
    )
  )
)
